# WIFI_SWICH.net
KiCad netlist of a schematic drawn in Altium Designer
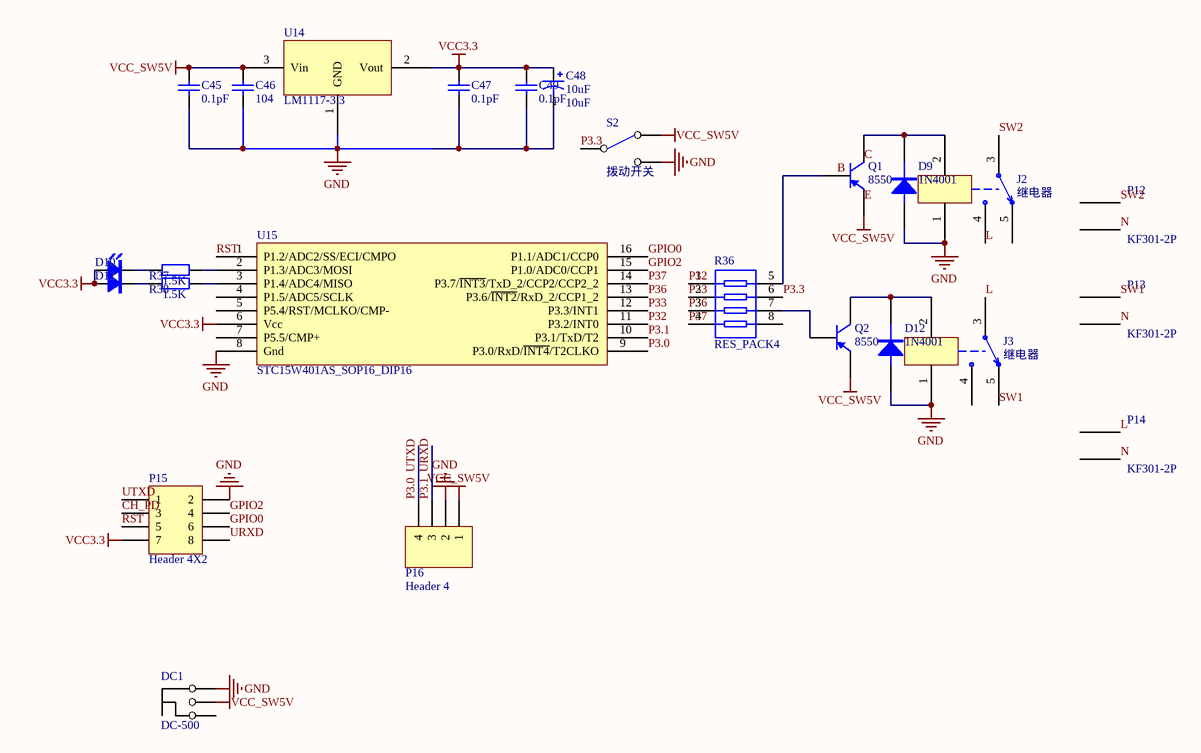
[diagram p0: WIFI_SWICH.SchDoc]

(export (version "E")
  (design (tool "Eeschema 10.0.6"))
  (components
    (comp (ref "C45")
      (value "0.1pF")
      (footprint "LC-0603_C")
      (description "Capacitor")
      (fields (field (name "Comment") "Cap") (field (name "PUBLISHER") "Altium Limited"))
      (libsource (lib "Miscellaneous Devices") (part "Cap"))
    )
    (comp (ref "C46")
      (value "104")
      (footprint "LC-Standard-FootPrints-AD-V1.00:LC-1210_C")
      (description "Capacitor")
      (fields (field (name "Comment") "Cap") (field (name "PUBLISHER") "Altium Limited"))
      (libsource (lib "Miscellaneous Devices") (part "Cap"))
    )
    (comp (ref "C47")
      (value "0.1pF")
      (footprint "LC-0603_C")
      (description "Capacitor")
      (fields (field (name "Comment") "Cap") (field (name "PUBLISHER") "Altium Limited"))
      (libsource (lib "Miscellaneous Devices") (part "Cap"))
    )
    (comp (ref "C48")
      (value "10uF")
      (footprint "LC-1210_C")
      (description "Polarized Capacitor (Radial)")
      (fields (field (name "ALTIUM_VALUE") "10uF") (field (name "PUBLISHER") "Altium Limited"))
      (libsource (lib "Miscellaneous Devices") (part "Cap Pol1"))
    )
    (comp (ref "C49")
      (value "0.1pF")
      (footprint "LC-0603_C")
      (description "Capacitor")
      (fields (field (name "Comment") "Cap") (field (name "PUBLISHER") "Altium Limited"))
      (libsource (lib "Miscellaneous Devices") (part "Cap"))
    )
    (comp (ref "D9") (value "1N4001") (footprint "SMA") (libsource (lib "ARAMYLIB") (part "1N4001")))
    (comp (ref "D10") (value "LED") (footprint "LC-0805_LED") (libsource (lib "MySchLib_1") (part "LED")))
    (comp (ref "D11") (value "LED") (footprint "LC-0805_LED") (libsource (lib "MySchLib_1") (part "LED")))
    (comp (ref "D12") (value "1N4001") (footprint "SMA") (libsource (lib "ARAMYLIB") (part "1N4001")))
    (comp (ref "DC1") (value "DC-500") (footprint "DC-005") (libsource (lib "ARAMYLIB") (part "DC-500")))
    (comp (ref "J2") (value "继电器") (footprint "继电器") (libsource (lib "自动浇花机") (part "继电器")))
    (comp (ref "J3") (value "继电器") (footprint "继电器") (libsource (lib "自动浇花机") (part "继电器")))
    (comp (ref "P12") (value "KF301-2P") (footprint "KF301-2P") (libsource (lib "ARAMYLIB") (part "接线柱")))
    (comp (ref "P13") (value "KF301-2P") (footprint "KF301-2P") (libsource (lib "ARAMYLIB") (part "接线柱")))
    (comp (ref "P14") (value "KF301-2P") (footprint "KF301-2P") (libsource (lib "ARAMYLIB") (part "接线柱")))
    (comp (ref "P15")
      (value "Header 4X2")
      (footprint "HDR2X4")
      (description "Header, 4-Pin, Dual row")
      (fields (field (name "PUBLISHER") "Altium Limited"))
      (libsource (lib "Miscellaneous Connectors") (part "Header 4X2"))
    )
    (comp (ref "P16")
      (value "Header 4")
      (footprint "HDR1X4")
      (description "Header, 4-Pin")
      (fields (field (name "PUBLISHER") "Altium Limited"))
      (libsource (lib "Miscellaneous Connectors") (part "Header 4"))
    )
    (comp (ref "Q1")
      (value "8550")
      (footprint "LC-SOT-23")
      (description "PNP General Purpose Amplifier")
      (fields (field (name "PUBLISHER") "Altium Limited"))
      (libsource (lib "Miscellaneous Devices") (part "2N3906"))
    )
    (comp (ref "Q2")
      (value "8550")
      (footprint "LC-SOT-23")
      (description "PNP General Purpose Amplifier")
      (fields (field (name "PUBLISHER") "Altium Limited"))
      (libsource (lib "Miscellaneous Devices") (part "2N3906"))
    )
    (comp (ref "R36") (value "RES_PACK4") (footprint "RES4") (libsource (lib "ARAMYLIB") (part "RES_PACK4")))
    (comp (ref "R37")
      (value "1.5K")
      (footprint "LC-0603_R")
      (description "Resistor")
      (fields (field (name "Comment") "Res2") (field (name "PUBLISHER") "Altium Limited"))
      (libsource (lib "MySchLib") (part "Res2"))
    )
    (comp (ref "R38")
      (value "1.5K")
      (footprint "LC-0603_R")
      (description "Resistor")
      (fields (field (name "Comment") "Res2") (field (name "PUBLISHER") "Altium Limited"))
      (libsource (lib "MySchLib") (part "Res2"))
    )
    (comp (ref "S2") (value "拨动开关") (footprint "拨动开关") (libsource (lib "ARAMYLIB") (part "拨动开关")))
    (comp (ref "U14")
      (value "LM1117-3.3")
      (footprint "SOT223")
      (libsource (lib "MySchLib") (part "LM1117-3.3"))
    )
    (comp (ref "U15")
      (value "STC15W401AS_SOP16_DIP16")
      (footprint "SOP16")
      (libsource (lib "stcmcu_altium_lib") (part "STC15W401AS_SOP16_DIP16"))
    )
  )
  (nets
    (net (code "3") (name "/CH_PD") (class "Default")
      (node (ref "P15") (pin "3") (pinfunction "3_3") (pintype "passive"))
    )
    (net (code "5") (name "/GPIO0") (class "Default")
      (node (ref "P15") (pin "6") (pinfunction "6_6") (pintype "passive"))
      (node (ref "U15") (pin "16") (pinfunction "P1.1/ADC1/CCP0_16") (pintype "passive"))
    )
    (net (code "6") (name "/GPIO2") (class "Default")
      (node (ref "P15") (pin "4") (pinfunction "4_4") (pintype "passive"))
      (node (ref "U15") (pin "15") (pinfunction "P1.0/ADC0/CCP1_15") (pintype "passive"))
    )
    (net (code "7") (name "/L") (class "Default")
      (node (ref "J2") (pin "4") (pintype "passive"))
      (node (ref "J3") (pin "3") (pintype "passive"))
      (node (ref "P14") (pin "0") (pinfunction "0_0") (pintype "passive"))
    )
    (net (code "8") (name "/N") (class "Default")
      (node (ref "P12") (pin "1") (pinfunction "1_1") (pintype "passive"))
      (node (ref "P13") (pin "1") (pinfunction "1_1") (pintype "passive"))
      (node (ref "P14") (pin "1") (pinfunction "1_1") (pintype "passive"))
    )
    (net (code "9") (name "/P3.0") (class "Default")
      (node (ref "P15") (pin "1") (pinfunction "1_1") (pintype "passive"))
      (node (ref "P16") (pin "4") (pinfunction "4_4") (pintype "passive"))
      (node (ref "U15") (pin "9") (pinfunction "P3.0/RxD/~{INT4}/T2CLKO_9") (pintype "passive"))
    )
    (net (code "10") (name "/P3.1") (class "Default")
      (node (ref "P15") (pin "8") (pinfunction "8_8") (pintype "passive"))
      (node (ref "P16") (pin "3") (pinfunction "3_3") (pintype "passive"))
      (node (ref "U15") (pin "10") (pinfunction "P3.1/TxD/T2_10") (pintype "passive"))
    )
    (net (code "11") (name "/P3.3") (class "Default")
      (node (ref "R36") (pin "6") (pinfunction "6_6") (pintype "passive"))
      (node (ref "S2") (pin "1") (pinfunction "COMMON1_1") (pintype "passive"))
    )
    (net (code "12") (name "/P32") (class "Default")
      (node (ref "R36") (pin "1") (pinfunction "1_1") (pintype "passive"))
      (node (ref "U15") (pin "11") (pinfunction "P3.2/INT0_11") (pintype "passive"))
    )
    (net (code "13") (name "/P33") (class "Default")
      (node (ref "R36") (pin "2") (pinfunction "2_2") (pintype "passive"))
      (node (ref "U15") (pin "12") (pinfunction "P3.3/INT1_12") (pintype "passive"))
    )
    (net (code "14") (name "/P36") (class "Default")
      (node (ref "R36") (pin "3") (pinfunction "3_3") (pintype "passive"))
      (node (ref "U15") (pin "13") (pinfunction "P3.6/~{INT2}/RxD_2/CCP1_2_13") (pintype "passive"))
    )
    (net (code "15") (name "/P37") (class "Default")
      (node (ref "R36") (pin "4") (pinfunction "4_4") (pintype "passive"))
      (node (ref "U15") (pin "14") (pinfunction "P3.7/~{INT3}/TxD_2/CCP2/CCP2_2_14") (pintype "passive"))
    )
    (net (code "16") (name "/RST") (class "Default")
      (node (ref "P15") (pin "5") (pinfunction "5_5") (pintype "passive"))
      (node (ref "U15") (pin "1") (pinfunction "P1.2/ADC2/SS/ECI/CMPO_1") (pintype "passive"))
    )
    (net (code "17") (name "/SW1") (class "Default")
      (node (ref "J3") (pin "5") (pintype "passive"))
      (node (ref "P13") (pin "0") (pinfunction "0_0") (pintype "passive"))
    )
    (net (code "18") (name "/SW2") (class "Default")
      (node (ref "J2") (pin "3") (pintype "passive"))
      (node (ref "P12") (pin "0") (pinfunction "0_0") (pintype "passive"))
    )
    (net (code "19") (name "GND") (class "Default")
      (node (ref "C45") (pin "2") (pinfunction "2_2") (pintype "passive"))
      (node (ref "C46") (pin "1") (pinfunction "1_1") (pintype "passive"))
      (node (ref "C47") (pin "2") (pinfunction "2_2") (pintype "passive"))
      (node (ref "C48") (pin "2") (pinfunction "2_2") (pintype "passive"))
      (node (ref "C49") (pin "2") (pinfunction "2_2") (pintype "passive"))
      (node (ref "D12") (pin "A") (pinfunction "1_A") (pintype "passive"))
      (node (ref "D9") (pin "A") (pinfunction "1_A") (pintype "passive"))
      (node (ref "DC1") (pin "1") (pinfunction "GND_1") (pintype "power_in"))
      (node (ref "J2") (pin "1") (pintype "passive"))
      (node (ref "J3") (pin "1") (pintype "passive"))
      (node (ref "P15") (pin "2") (pinfunction "2_2") (pintype "passive"))
      (node (ref "P16") (pin "2") (pinfunction "2_2") (pintype "passive"))
      (node (ref "S2") (pin "3") (pinfunction "NO1_3") (pintype "passive"))
      (node (ref "U14") (pin "1") (pinfunction "GND_1") (pintype "passive"))
      (node (ref "U15") (pin "8") (pinfunction "Gnd_8") (pintype "passive"))
    )
    (net (code "20") (name "Net-(D9-2)") (class "Default")
      (node (ref "D9") (pin "K") (pinfunction "2_K") (pintype "passive"))
      (node (ref "J2") (pin "2") (pintype "passive"))
      (node (ref "Q1") (pin "3") (pinfunction "C_3") (pintype "passive"))
    )
    (net (code "21") (name "Net-(D10-Pad2)") (class "Default")
      (node (ref "D10") (pin "2") (pinfunction "2_2") (pintype "passive"))
      (node (ref "R37") (pin "1") (pinfunction "1_1") (pintype "passive"))
    )
    (net (code "22") (name "Net-(D11-Pad2)") (class "Default")
      (node (ref "D11") (pin "2") (pinfunction "2_2") (pintype "passive"))
      (node (ref "R38") (pin "1") (pinfunction "1_1") (pintype "passive"))
    )
    (net (code "23") (name "Net-(D12-2)") (class "Default")
      (node (ref "D12") (pin "K") (pinfunction "2_K") (pintype "passive"))
      (node (ref "J3") (pin "2") (pintype "passive"))
      (node (ref "Q2") (pin "3") (pinfunction "C_3") (pintype "passive"))
    )
    (net (code "24") (name "Net-(Q1-B)") (class "Default")
      (node (ref "Q1") (pin "2") (pinfunction "B_2") (pintype "passive"))
      (node (ref "R36") (pin "5") (pinfunction "5_5") (pintype "passive"))
    )
    (net (code "25") (name "Net-(Q2-B)") (class "Default")
      (node (ref "Q2") (pin "2") (pinfunction "B_2") (pintype "passive"))
      (node (ref "R36") (pin "7") (pinfunction "7_7") (pintype "passive"))
    )
    (net (code "26") (name "Net-(U15-P1.3{slash}ADC3{slash}MOSI)") (class "Default")
      (node (ref "R37") (pin "2") (pinfunction "2_2") (pintype "passive"))
      (node (ref "U15") (pin "2") (pinfunction "P1.3/ADC3/MOSI_2") (pintype "passive"))
    )
    (net (code "27") (name "Net-(U15-P1.4{slash}ADC4{slash}MISO)") (class "Default")
      (node (ref "R38") (pin "2") (pinfunction "2_2") (pintype "passive"))
      (node (ref "U15") (pin "3") (pinfunction "P1.4/ADC4/MISO_3") (pintype "passive"))
    )
    (net (code "28") (name "VCC3.3") (class "Default")
      (node (ref "C47") (pin "1") (pinfunction "1_1") (pintype "passive"))
      (node (ref "C48") (pin "1") (pinfunction "1_1") (pintype "passive"))
      (node (ref "C49") (pin "1") (pinfunction "1_1") (pintype "passive"))
      (node (ref "D10") (pin "1") (pinfunction "1_1") (pintype "passive"))
      (node (ref "D11") (pin "1") (pinfunction "1_1") (pintype "passive"))
      (node (ref "P15") (pin "7") (pinfunction "7_7") (pintype "passive"))
      (node (ref "U14") (pin "2") (pinfunction "Vout_2") (pintype "passive"))
      (node (ref "U15") (pin "6") (pinfunction "Vcc_6") (pintype "passive"))
    )
    (net (code "29") (name "VCC_SW5V") (class "Default")
      (node (ref "C45") (pin "1") (pinfunction "1_1") (pintype "passive"))
      (node (ref "C46") (pin "2") (pinfunction "2_2") (pintype "passive"))
      (node (ref "DC1") (pin "2") (pinfunction "POW_2") (pintype "power_in"))
      (node (ref "P16") (pin "1") (pinfunction "1_1") (pintype "passive"))
      (node (ref "Q1") (pin "1") (pinfunction "E_1") (pintype "passive"))
      (node (ref "Q2") (pin "1") (pinfunction "E_1") (pintype "passive"))
      (node (ref "S2") (pin "2") (pinfunction "NC1_2") (pintype "passive"))
      (node (ref "U14") (pin "3") (pinfunction "Vin_3") (pintype "passive"))
    )
    (net (code "30") (name "unconnected-(DC1-KEY-Pad3)") (class "Default")
      (node (ref "DC1") (pin "3") (pinfunction "KEY_3") (pintype "power_in"))
    )
    (net (code "31") (name "unconnected-(J2-Pad5)") (class "Default")
      (node (ref "J2") (pin "5") (pintype "passive"))
    )
    (net (code "32") (name "unconnected-(J3-Pad4)") (class "Default")
      (node (ref "J3") (pin "4") (pintype "passive"))
    )
    (net (code "33") (name "unconnected-(R36-Pad8)") (class "Default")
      (node (ref "R36") (pin "8") (pinfunction "8_8") (pintype "passive"))
    )
    (net (code "34") (name "unconnected-(U15-P1.5{slash}ADC5{slash}SCLK-Pad4)") (class "Default")
      (node (ref "U15") (pin "4") (pinfunction "P1.5/ADC5/SCLK_4") (pintype "passive"))
    )
    (net (code "35") (name "unconnected-(U15-P5.4{slash}RST{slash}MCLKO{slash}CMP--Pad5)") (class "Default")
      (node (ref "U15") (pin "5") (pinfunction "P5.4/RST/MCLKO/CMP-_5") (pintype "passive"))
    )
    (net (code "36") (name "unconnected-(U15-P5.5{slash}CMP+-Pad7)") (class "Default")
      (node (ref "U15") (pin "7") (pinfunction "P5.5/CMP+_7") (pintype "passive"))
    )
  )
)
